# Board_C22.net
KiCad netlist of a schematic drawn in Altium Designer
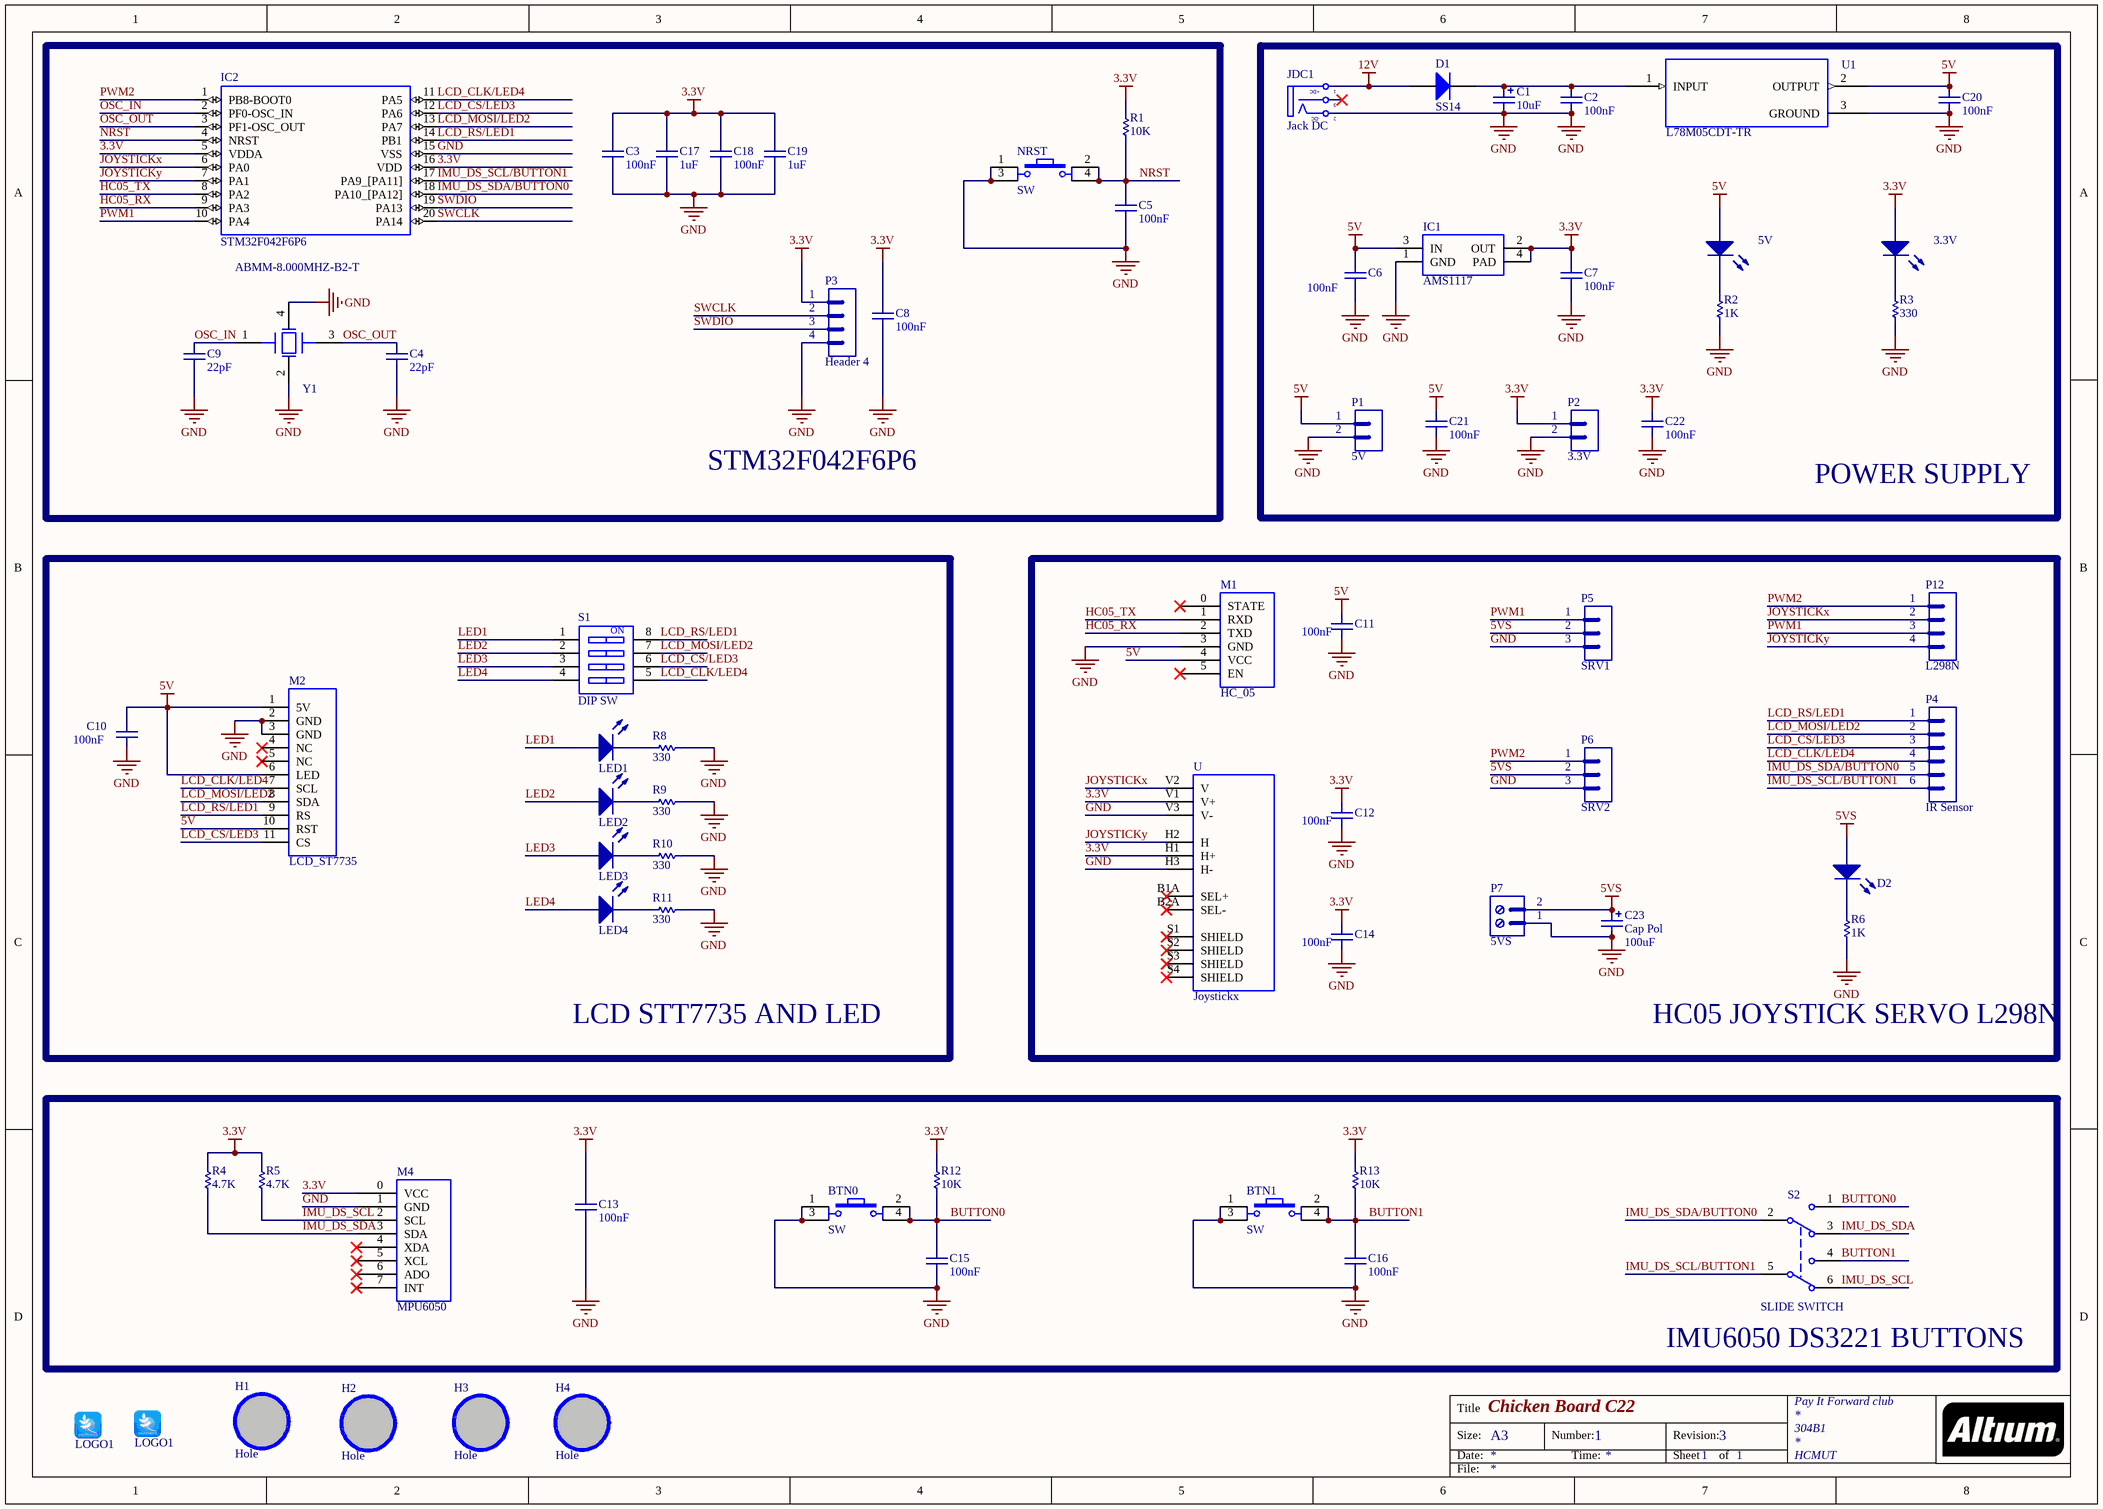
[diagram p0: Board_C22.SchDoc]

(export (version "E")
  (design (tool "Eeschema 10.0.6"))
  (components
    (comp (ref "3.3V") (value "LED") (footprint "LED_0805_Blue") (libsource (lib "Board_C22") (part "LED")))
    (comp (ref "5V") (value "LED") (footprint "LED_0805_Blue") (libsource (lib "Board_C22") (part "LED")))
    (comp (ref "BTN0")
      (value "SW")
      (footprint "4301x60437x6")
      (description "Switch button 4 pin")
      (libsource (lib "Board_C22") (part "SW4"))
    )
    (comp (ref "BTN1")
      (value "SW")
      (footprint "4301x60437x6")
      (description "Switch button 4 pin")
      (libsource (lib "Board_C22") (part "SW4"))
    )
    (comp (ref "C1")
      (value "Capacitors")
      (footprint "C_TANTALUM_3216_18")
      (description "Capacitors Tantalum")
      (fields
        (field (name "MANUFACTURER") "Kemet")
        (field (name "MANUFACTURER PART NUMBER") "T491A106K010AT")
        (field (name "CAPACITANCE") "10uF")
      )
      (libsource (lib "Board_C22") (part "Cap Pol Tantalum"))
    )
    (comp (ref "C2")
      (value "100nF")
      (footprint "CAP-SM-0805")
      (description "Capacitor")
      (fields (field (name "Comment") "Cap Non-Pol SMD"))
      (libsource (lib "Board_C22") (part "Cap Non-Pol SMD"))
    )
    (comp (ref "C3")
      (value "100nF")
      (footprint "CAP-SM-0805")
      (description "Capacitor")
      (fields (field (name "Comment") "Cap Non-Pol SMD"))
      (libsource (lib "Board_C22") (part "Cap Non-Pol SMD"))
    )
    (comp (ref "C4")
      (value "22pF")
      (footprint "CAP-SM-0805")
      (description "Capacitor")
      (fields (field (name "Comment") "Cap Non-Pol SMD"))
      (libsource (lib "Board_C22") (part "Cap Non-Pol SMD"))
    )
    (comp (ref "C5")
      (value "100nF")
      (footprint "CAP-SM-0805")
      (description "Capacitor")
      (fields (field (name "Comment") "Cap Non-Pol SMD"))
      (libsource (lib "Board_C22") (part "Cap Non-Pol SMD"))
    )
    (comp (ref "C6")
      (value "100nF")
      (footprint "CAP-SM-0805")
      (description "Capacitor")
      (fields (field (name "Comment") "Cap Non-Pol SMD"))
      (libsource (lib "Board_C22") (part "Cap Non-Pol SMD"))
    )
    (comp (ref "C7")
      (value "100nF")
      (footprint "CAP-SM-0805")
      (description "Capacitor")
      (fields (field (name "Comment") "Cap Non-Pol SMD"))
      (libsource (lib "Board_C22") (part "Cap Non-Pol SMD"))
    )
    (comp (ref "C8")
      (value "100nF")
      (footprint "CAP-SM-0805")
      (description "Capacitor")
      (fields (field (name "Comment") "Cap Non-Pol SMD"))
      (libsource (lib "Board_C22") (part "Cap Non-Pol SMD"))
    )
    (comp (ref "C9")
      (value "22pF")
      (footprint "CAP-SM-0805")
      (description "Capacitor")
      (fields (field (name "Comment") "Cap Non-Pol SMD"))
      (libsource (lib "Board_C22") (part "Cap Non-Pol SMD"))
    )
    (comp (ref "C10")
      (value "100nF")
      (footprint "CAP-SM-0805")
      (description "Capacitor")
      (fields (field (name "Comment") "Cap Non-Pol SMD"))
      (libsource (lib "Board_C22") (part "Cap Non-Pol SMD"))
    )
    (comp (ref "C11")
      (value "100nF")
      (footprint "CAP-SM-0805")
      (description "Capacitor")
      (fields (field (name "Comment") "Cap Non-Pol SMD"))
      (libsource (lib "Board_C22") (part "Cap Non-Pol SMD"))
    )
    (comp (ref "C12")
      (value "100nF")
      (footprint "CAP-SM-0805")
      (description "Capacitor")
      (fields (field (name "Comment") "Cap Non-Pol SMD"))
      (libsource (lib "Board_C22") (part "Cap Non-Pol SMD"))
    )
    (comp (ref "C13")
      (value "100nF")
      (footprint "CAP-SM-0805")
      (description "Capacitor")
      (fields (field (name "Comment") "Cap Non-Pol SMD"))
      (libsource (lib "Board_C22") (part "Cap Non-Pol SMD"))
    )
    (comp (ref "C14")
      (value "100nF")
      (footprint "CAP-SM-0805")
      (description "Capacitor")
      (fields (field (name "Comment") "Cap Non-Pol SMD"))
      (libsource (lib "Board_C22") (part "Cap Non-Pol SMD"))
    )
    (comp (ref "C15")
      (value "100nF")
      (footprint "CAP-SM-0805")
      (description "Capacitor")
      (fields (field (name "Comment") "Cap Non-Pol SMD"))
      (libsource (lib "Board_C22") (part "Cap Non-Pol SMD"))
    )
    (comp (ref "C16")
      (value "100nF")
      (footprint "CAP-SM-0805")
      (description "Capacitor")
      (fields (field (name "Comment") "Cap Non-Pol SMD"))
      (libsource (lib "Board_C22") (part "Cap Non-Pol SMD"))
    )
    (comp (ref "C17")
      (value "1uF")
      (footprint "CAP-SM-0805")
      (description "Capacitor")
      (fields (field (name "Comment") "Cap Non-Pol SMD"))
      (libsource (lib "Board_C22") (part "Cap Non-Pol SMD"))
    )
    (comp (ref "C18")
      (value "100nF")
      (footprint "CAP-SM-0805")
      (description "Capacitor")
      (fields (field (name "Comment") "Cap Non-Pol SMD"))
      (libsource (lib "Board_C22") (part "Cap Non-Pol SMD"))
    )
    (comp (ref "C19")
      (value "1uF")
      (footprint "CAP-SM-0805")
      (description "Capacitor")
      (fields (field (name "Comment") "Cap Non-Pol SMD"))
      (libsource (lib "Board_C22") (part "Cap Non-Pol SMD"))
    )
    (comp (ref "C20")
      (value "100nF")
      (footprint "CAP-SM-0805")
      (description "Capacitor")
      (fields (field (name "Comment") "Cap Non-Pol SMD"))
      (libsource (lib "Board_C22") (part "Cap Non-Pol SMD"))
    )
    (comp (ref "C21")
      (value "100nF")
      (footprint "CAP-SM-0805")
      (description "Capacitor")
      (fields (field (name "Comment") "Cap Non-Pol SMD"))
      (libsource (lib "Board_C22") (part "Cap Non-Pol SMD"))
    )
    (comp (ref "C22")
      (value "100nF")
      (footprint "CAP-SM-0805")
      (description "Capacitor")
      (fields (field (name "Comment") "Cap Non-Pol SMD"))
      (libsource (lib "Board_C22") (part "Cap Non-Pol SMD"))
    )
    (comp (ref "C23")
      (value "Cap Pol")
      (footprint "CP1/2.5")
      (description "Polarized Capacitor (Radial)")
      (fields (field (name "ALTIUM_VALUE") "100uF"))
      (libsource (lib "Board_C22") (part "Cap Pol"))
    )
    (comp (ref "D1")
      (value "SS14")
      (footprint "SS14")
      (description "DIODE SCHOTTKY 40V 1A SMA")
      (fields (field (name "MANUFACTURER") "ON Semiconductor"))
      (libsource (lib "Board_C22") (part "Diode-SS14"))
    )
    (comp (ref "D2") (value "LED") (footprint "LED_0805_Blue") (libsource (lib "Board_C22") (part "LED")))
    (comp (ref "H1")
      (value "Hole")
      (footprint "LO KHOAN 3MM")
      (description "Hole 3mm")
      (libsource (lib "Board_C22") (part "Hole"))
    )
    (comp (ref "H2")
      (value "Hole")
      (footprint "LO KHOAN 3MM")
      (description "Hole 3mm")
      (libsource (lib "Board_C22") (part "Hole"))
    )
    (comp (ref "H3")
      (value "Hole")
      (footprint "LO KHOAN 3MM")
      (description "Hole 3mm")
      (libsource (lib "Board_C22") (part "Hole"))
    )
    (comp (ref "H4")
      (value "Hole")
      (footprint "LO KHOAN 3MM")
      (description "Hole 3mm")
      (libsource (lib "Board_C22") (part "Hole"))
    )
    (comp (ref "IC1")
      (value "AMS1117")
      (footprint "SOT223")
      (description "Available in 1.8V, 2.5V, 2.85V, 3.3V, 5V, and  Adjustable Versions")
      (libsource (lib "Board_C22") (part "AMS1117"))
    )
    (comp (ref "IC2")
      (value "STM32F042F6P6")
      (footprint "TSSOP20")
      (description "ARMÂ® CortexÂ®-M0 STM32F0 Microcontroller IC 32-Bit 48MHz 32KB _32K x 8_ FLASH 20-TSSOP")
      (fields (field (name "MF") "STMicroelectronics"))
      (libsource (lib "Board_C22") (part "STM32F042F6P6"))
    )
    (comp (ref "JDC1")
      (value "Jack DC")
      (footprint "DC-IN")
      (description "Jack DC input")
      (libsource (lib "Board_C22") (part "Jack DC"))
    )
    (comp (ref "LED1") (value "LED") (footprint "LED_0805_Blue") (libsource (lib "Board_C22") (part "LED")))
    (comp (ref "LED2") (value "LED") (footprint "LED_0805_Blue") (libsource (lib "Board_C22") (part "LED")))
    (comp (ref "LED3") (value "LED") (footprint "LED_0805_Blue") (libsource (lib "Board_C22") (part "LED")))
    (comp (ref "LED4") (value "LED") (footprint "LED_0805_Blue") (libsource (lib "Board_C22") (part "LED")))
    (comp (ref "M1") (value "HC_05") (footprint "HC_05") (libsource (lib "Board_C22") (part "HC_05")))
    (comp (ref "M2")
      (value "LCD_ST7735")
      (footprint "LCD_ST7735")
      (libsource (lib "Board_C22") (part "LCD_ST7735"))
    )
    (comp (ref "M4")
      (value "MPU6050")
      (footprint "GY521_MPU6050")
      (libsource (lib "Board_C22") (part "GY521_MPU6050"))
    )
    (comp (ref "NRST")
      (value "SW")
      (footprint "4301x60437x6")
      (description "Switch button 4 pin")
      (libsource (lib "Board_C22") (part "SW4"))
    )
    (comp (ref "P1")
      (value "5V")
      (footprint "JP2")
      (description "Header, 2-Pin")
      (fields (field (name "PUBLISHER") "Altium Limited"))
      (libsource (lib "Board_C22") (part "Header 2"))
    )
    (comp (ref "P2")
      (value "3.3V")
      (footprint "JP2")
      (description "Header, 2-Pin")
      (fields (field (name "PUBLISHER") "Altium Limited"))
      (libsource (lib "Board_C22") (part "Header 2"))
    )
    (comp (ref "P3")
      (value "Header 4")
      (footprint "JP4")
      (description "Header, 4-Pin")
      (fields (field (name "PUBLISHER") "Altium Limited"))
      (libsource (lib "Board_C22") (part "Header 4"))
    )
    (comp (ref "P4")
      (value "IR Sensor")
      (footprint "JP6")
      (description "Header, 6-Pin")
      (fields (field (name "PUBLISHER") "Altium Limited"))
      (libsource (lib "Board_C22") (part "Header 6"))
    )
    (comp (ref "P5")
      (value "SRV1")
      (footprint "JP3")
      (description "Header, 3-Pin")
      (fields (field (name "PUBLISHER") "Altium Limited"))
      (libsource (lib "Board_C22") (part "Header 3"))
    )
    (comp (ref "P6")
      (value "SRV2")
      (footprint "JP3")
      (description "Header, 3-Pin")
      (fields (field (name "PUBLISHER") "Altium Limited"))
      (libsource (lib "Board_C22") (part "Header 3"))
    )
    (comp (ref "P7")
      (value "5VS")
      (footprint "DOMINO SMALL 2")
      (description "Domino, 2-Pin")
      (fields (field (name "PUBLISHER") "Altium Limited"))
      (libsource (lib "Board_C22") (part "Domino 2"))
    )
    (comp (ref "P12")
      (value "L298N")
      (footprint "JP4")
      (description "Header, 4-Pin")
      (fields (field (name "PUBLISHER") "Altium Limited"))
      (libsource (lib "Board_C22") (part "Header 4"))
    )
    (comp (ref "R1")
      (value "10K")
      (footprint "RES-SM-0805")
      (fields (field (name "Comment") "Resistor 1/4W"))
      (libsource (lib "Board_C22") (part "RES"))
    )
    (comp (ref "R2")
      (value "1K")
      (footprint "RES-SM-0805")
      (fields (field (name "Comment") "Resistor 1/4W"))
      (libsource (lib "Board_C22") (part "RES"))
    )
    (comp (ref "R3")
      (value "330")
      (footprint "RES-SM-0805")
      (fields (field (name "Comment") "Resistor 1/4W"))
      (libsource (lib "Board_C22") (part "RES"))
    )
    (comp (ref "R4")
      (value "4.7K")
      (footprint "RES-SM-0805")
      (fields (field (name "Comment") "Resistor 1/4W"))
      (libsource (lib "Board_C22") (part "RES"))
    )
    (comp (ref "R5")
      (value "4.7K")
      (footprint "RES-SM-0805")
      (fields (field (name "Comment") "Resistor 1/4W"))
      (libsource (lib "Board_C22") (part "RES"))
    )
    (comp (ref "R6")
      (value "1K")
      (footprint "RES-SM-0805")
      (fields (field (name "Comment") "Resistor 1/4W"))
      (libsource (lib "Board_C22") (part "RES"))
    )
    (comp (ref "R8")
      (value "330")
      (footprint "RES-SM-0805")
      (fields (field (name "Comment") "Resistor 1/4W"))
      (libsource (lib "Board_C22") (part "RES"))
    )
    (comp (ref "R9")
      (value "330")
      (footprint "RES-SM-0805")
      (fields (field (name "Comment") "Resistor 1/4W"))
      (libsource (lib "Board_C22") (part "RES"))
    )
    (comp (ref "R10")
      (value "330")
      (footprint "RES-SM-0805")
      (fields (field (name "Comment") "Resistor 1/4W"))
      (libsource (lib "Board_C22") (part "RES"))
    )
    (comp (ref "R11")
      (value "330")
      (footprint "RES-SM-0805")
      (fields (field (name "Comment") "Resistor 1/4W"))
      (libsource (lib "Board_C22") (part "RES"))
    )
    (comp (ref "R12")
      (value "10K")
      (footprint "RES-SM-0805")
      (fields (field (name "Comment") "Resistor 1/4W"))
      (libsource (lib "Board_C22") (part "RES"))
    )
    (comp (ref "R13")
      (value "10K")
      (footprint "RES-SM-0805")
      (fields (field (name "Comment") "Resistor 1/4W"))
      (libsource (lib "Board_C22") (part "RES"))
    )
    (comp (ref "S1")
      (value "DIP SW")
      (footprint "418117270904")
      (description "WS-DITV Compact THT Dip Switch, Raised Actuator, pitch 2.54mm, 4p")
      (fields (field (name "PART NUMBER") "418117270904") (field (name "PUBLISHER") "Wurth Elektronik"))
      (libsource (lib "Board_C22") (part "DIP SW"))
    )
    (comp (ref "S2")
      (value "SLIDE SWITCH")
      (footprint "452404020202")
      (description "WS-SLTV THT Mini Slide Switch, Same Side Connection, DPDT")
      (fields (field (name "PART NUMBER") "452404020202") (field (name "PUBLISHER") "Wurth Elektronik"))
      (libsource (lib "Board_C22") (part "SW"))
    )
    (comp (ref "U")
      (value "Joystickx")
      (footprint "XDCR_COM-09032")
      (description "Joystick, 2 - Axis Analog _Resistive_ Output")
      (fields (field (name "MF") "SparkFun Electronics") (field (name "MP") "COM-09032"))
      (libsource (lib "Board_C22") (part "Joystickx"))
    )
    (comp (ref "U1")
      (value "L78M05CDT-TR")
      (footprint "DPAK_STM")
      (description "No Description Available")
      (fields (field (name "COPYRIGHT") "Copyright (C) 2018 Accelerated Designs. All rights reserved"))
      (libsource (lib "Board_C22") (part "L78M05CDT-TR"))
    )
    (comp (ref "Y1")
      (value "ABMM-8.000MHZ-B2-T")
      (footprint "XTAL_TSX-3225_16.0000MF18X-AC3")
      (description "8MHz Â±20ppm Crystal 18pF 70 Ohms 4-SMD, No Lead")
      (fields (field (name "MF") "Abracon") (field (name "DIGI-KEY_PART_NUMBER") "535-9164-1-ND"))
      (libsource (lib "Board_C22") (part "ABMM-8.000MHZ-B2-T"))
    )
  )
  (nets
    (net (code "1") (name "/BUTTON0") (class "Default")
      (node (ref "BTN0") (pin "2") (pintype "passive"))
      (node (ref "BTN0") (pin "4") (pintype "passive"))
      (node (ref "C15") (pin "2") (pinfunction "2_2") (pintype "passive"))
      (node (ref "R12") (pin "1") (pintype "passive"))
      (node (ref "S2") (pin "1") (pinfunction "1_1") (pintype "passive"))
    )
    (net (code "2") (name "/BUTTON1") (class "Default")
      (node (ref "BTN1") (pin "2") (pintype "passive"))
      (node (ref "BTN1") (pin "4") (pintype "passive"))
      (node (ref "C16") (pin "2") (pinfunction "2_2") (pintype "passive"))
      (node (ref "R13") (pin "1") (pintype "passive"))
      (node (ref "S2") (pin "4") (pinfunction "4_4") (pintype "passive"))
    )
    (net (code "3") (name "/HC05_RX") (class "Default")
      (node (ref "IC2") (pin "9") (pinfunction "PA3_9") (pintype "bidirectional"))
      (node (ref "M1") (pin "2") (pinfunction "TXD_2") (pintype "passive"))
    )
    (net (code "4") (name "/HC05_TX") (class "Default")
      (node (ref "IC2") (pin "8") (pinfunction "PA2_8") (pintype "bidirectional"))
      (node (ref "M1") (pin "1") (pinfunction "RXD_1") (pintype "passive"))
    )
    (net (code "5") (name "/IMU_DS_SCL") (class "Default")
      (node (ref "M4") (pin "2") (pinfunction "SCL_2") (pintype "passive"))
      (node (ref "R5") (pin "1") (pintype "passive"))
      (node (ref "S2") (pin "6") (pinfunction "6_6") (pintype "passive"))
    )
    (net (code "6") (name "/IMU_DS_SCL{slash}BUTTON1") (class "Default")
      (node (ref "IC2") (pin "17") (pinfunction "PA9_[PA11]_17") (pintype "bidirectional"))
      (node (ref "P4") (pin "6") (pinfunction "6_6") (pintype "passive"))
      (node (ref "S2") (pin "5") (pinfunction "COM_5") (pintype "passive"))
    )
    (net (code "7") (name "/IMU_DS_SDA") (class "Default")
      (node (ref "M4") (pin "3") (pinfunction "SDA_3") (pintype "passive"))
      (node (ref "R4") (pin "1") (pintype "passive"))
      (node (ref "S2") (pin "3") (pinfunction "3_3") (pintype "passive"))
    )
    (net (code "8") (name "/IMU_DS_SDA{slash}BUTTON0") (class "Default")
      (node (ref "IC2") (pin "18") (pinfunction "PA10_[PA12]_18") (pintype "bidirectional"))
      (node (ref "P4") (pin "5") (pinfunction "5_5") (pintype "passive"))
      (node (ref "S2") (pin "2") (pinfunction "COM_2") (pintype "passive"))
    )
    (net (code "9") (name "/JOYSTICKx") (class "Default")
      (node (ref "IC2") (pin "6") (pinfunction "PA0_6") (pintype "bidirectional"))
      (node (ref "P12") (pin "2") (pinfunction "2_2") (pintype "passive"))
      (node (ref "U") (pin "V2") (pinfunction "V_V2") (pintype "passive"))
    )
    (net (code "10") (name "/JOYSTICKy") (class "Default")
      (node (ref "IC2") (pin "7") (pinfunction "PA1_7") (pintype "bidirectional"))
      (node (ref "P12") (pin "4") (pinfunction "4_4") (pintype "passive"))
      (node (ref "U") (pin "H2") (pinfunction "H_H2") (pintype "passive"))
    )
    (net (code "11") (name "/LCD_CLK{slash}LED4") (class "Default")
      (node (ref "IC2") (pin "11") (pinfunction "PA5_11") (pintype "bidirectional"))
      (node (ref "M2") (pin "7") (pinfunction "SCL_7") (pintype "passive"))
      (node (ref "P4") (pin "4") (pinfunction "4_4") (pintype "passive"))
      (node (ref "S1") (pin "5") (pinfunction "5_5") (pintype "passive"))
    )
    (net (code "12") (name "/LCD_CS{slash}LED3") (class "Default")
      (node (ref "IC2") (pin "12") (pinfunction "PA6_12") (pintype "bidirectional"))
      (node (ref "M2") (pin "11") (pinfunction "CS_11") (pintype "passive"))
      (node (ref "P4") (pin "3") (pinfunction "3_3") (pintype "passive"))
      (node (ref "S1") (pin "6") (pinfunction "6_6") (pintype "passive"))
    )
    (net (code "13") (name "/LCD_MOSI{slash}LED2") (class "Default")
      (node (ref "IC2") (pin "13") (pinfunction "PA7_13") (pintype "bidirectional"))
      (node (ref "M2") (pin "8") (pinfunction "SDA_8") (pintype "passive"))
      (node (ref "P4") (pin "2") (pinfunction "2_2") (pintype "passive"))
      (node (ref "S1") (pin "7") (pinfunction "7_7") (pintype "passive"))
    )
    (net (code "14") (name "/LCD_RS{slash}LED1") (class "Default")
      (node (ref "IC2") (pin "14") (pinfunction "PB1_14") (pintype "bidirectional"))
      (node (ref "M2") (pin "9") (pinfunction "RS_9") (pintype "passive"))
      (node (ref "P4") (pin "1") (pinfunction "1_1") (pintype "passive"))
      (node (ref "S1") (pin "8") (pinfunction "8_8") (pintype "passive"))
    )
    (net (code "15") (name "/LED1") (class "Default")
      (node (ref "LED1") (pin "1") (pinfunction "A_1") (pintype "passive"))
      (node (ref "S1") (pin "1") (pinfunction "1_1") (pintype "passive"))
    )
    (net (code "16") (name "/LED2") (class "Default")
      (node (ref "LED2") (pin "1") (pinfunction "A_1") (pintype "passive"))
      (node (ref "S1") (pin "2") (pinfunction "2_2") (pintype "passive"))
    )
    (net (code "17") (name "/LED3") (class "Default")
      (node (ref "LED3") (pin "1") (pinfunction "A_1") (pintype "passive"))
      (node (ref "S1") (pin "3") (pinfunction "3_3") (pintype "passive"))
    )
    (net (code "18") (name "/LED4") (class "Default")
      (node (ref "LED4") (pin "1") (pinfunction "A_1") (pintype "passive"))
      (node (ref "S1") (pin "4") (pinfunction "4_4") (pintype "passive"))
    )
    (net (code "19") (name "/NRST") (class "Default")
      (node (ref "C5") (pin "2") (pinfunction "2_2") (pintype "passive"))
      (node (ref "IC2") (pin "4") (pinfunction "NRST_4") (pintype "bidirectional"))
      (node (ref "NRST") (pin "2") (pintype "passive"))
      (node (ref "NRST") (pin "4") (pintype "passive"))
      (node (ref "R1") (pin "1") (pintype "passive"))
    )
    (net (code "20") (name "/OSC_IN") (class "Default")
      (node (ref "C9") (pin "1") (pinfunction "1_1") (pintype "passive"))
      (node (ref "IC2") (pin "2") (pinfunction "PF0-OSC_IN_2") (pintype "bidirectional"))
      (node (ref "Y1") (pin "1") (pintype "passive"))
    )
    (net (code "21") (name "/OSC_OUT") (class "Default")
      (node (ref "C4") (pin "2") (pinfunction "2_2") (pintype "passive"))
      (node (ref "IC2") (pin "3") (pinfunction "PF1-OSC_OUT_3") (pintype "bidirectional"))
      (node (ref "Y1") (pin "3") (pintype "passive"))
    )
    (net (code "22") (name "/PWM1") (class "Default")
      (node (ref "IC2") (pin "10") (pinfunction "PA4_10") (pintype "bidirectional"))
      (node (ref "P12") (pin "3") (pinfunction "3_3") (pintype "passive"))
      (node (ref "P5") (pin "1") (pinfunction "1_1") (pintype "passive"))
    )
    (net (code "23") (name "/PWM2") (class "Default")
      (node (ref "IC2") (pin "1") (pinfunction "PB8-BOOT0_1") (pintype "bidirectional"))
      (node (ref "P12") (pin "1") (pinfunction "1_1") (pintype "passive"))
      (node (ref "P6") (pin "1") (pinfunction "1_1") (pintype "passive"))
    )
    (net (code "24") (name "/SWCLK") (class "Default")
      (node (ref "IC2") (pin "20") (pinfunction "PA14_20") (pintype "bidirectional"))
      (node (ref "P3") (pin "2") (pinfunction "2_2") (pintype "passive"))
    )
    (net (code "25") (name "/SWDIO") (class "Default")
      (node (ref "IC2") (pin "19") (pinfunction "PA13_19") (pintype "bidirectional"))
      (node (ref "P3") (pin "3") (pinfunction "3_3") (pintype "passive"))
    )
    (net (code "26") (name "3.3V") (class "Default")
      (node (ref "3.3V") (pin "1") (pinfunction "A_1") (pintype "passive"))
      (node (ref "C12") (pin "2") (pinfunction "2_2") (pintype "passive"))
      (node (ref "C13") (pin "2") (pinfunction "2_2") (pintype "passive"))
      (node (ref "C14") (pin "2") (pinfunction "2_2") (pintype "passive"))
      (node (ref "C17") (pin "2") (pinfunction "2_2") (pintype "passive"))
      (node (ref "C18") (pin "2") (pinfunction "2_2") (pintype "passive"))
      (node (ref "C19") (pin "2") (pinfunction "2_2") (pintype "passive"))
      (node (ref "C22") (pin "2") (pinfunction "2_2") (pintype "passive"))
      (node (ref "C3") (pin "2") (pinfunction "2_2") (pintype "passive"))
      (node (ref "C7") (pin "2") (pinfunction "2_2") (pintype "passive"))
      (node (ref "C8") (pin "2") (pinfunction "2_2") (pintype "passive"))
      (node (ref "IC1") (pin "2") (pinfunction "OUT_2") (pintype "passive"))
      (node (ref "IC1") (pin "4") (pinfunction "PAD_4") (pintype "passive"))
      (node (ref "IC2") (pin "16") (pinfunction "VDD_16") (pintype "bidirectional"))
      (node (ref "IC2") (pin "5") (pinfunction "VDDA_5") (pintype "bidirectional"))
      (node (ref "M4") (pin "0") (pinfunction "VCC_0") (pintype "passive"))
      (node (ref "P2") (pin "1") (pinfunction "1_1") (pintype "passive"))
      (node (ref "P3") (pin "1") (pinfunction "1_1") (pintype "passive"))
      (node (ref "R1") (pin "2") (pintype "passive"))
      (node (ref "R12") (pin "2") (pintype "passive"))
      (node (ref "R13") (pin "2") (pintype "passive"))
      (node (ref "R4") (pin "2") (pintype "passive"))
      (node (ref "R5") (pin "2") (pintype "passive"))
      (node (ref "U") (pin "H1") (pinfunction "H+_H1") (pintype "passive"))
      (node (ref "U") (pin "V1") (pinfunction "V+_V1") (pintype "passive"))
    )
    (net (code "27") (name "5V") (class "Default")
      (node (ref "5V") (pin "1") (pinfunction "A_1") (pintype "passive"))
      (node (ref "C10") (pin "2") (pinfunction "2_2") (pintype "passive"))
      (node (ref "C11") (pin "2") (pinfunction "2_2") (pintype "passive"))
      (node (ref "C20") (pin "1") (pinfunction "1_1") (pintype "passive"))
      (node (ref "C21") (pin "2") (pinfunction "2_2") (pintype "passive"))
      (node (ref "C6") (pin "2") (pinfunction "2_2") (pintype "passive"))
      (node (ref "IC1") (pin "3") (pinfunction "IN_3") (pintype "passive"))
      (node (ref "M1") (pin "4") (pinfunction "VCC_4") (pintype "passive"))
      (node (ref "M2") (pin "1") (pinfunction "5V_1") (pintype "passive"))
      (node (ref "M2") (pin "10") (pinfunction "RST_10") (pintype "passive"))
      (node (ref "M2") (pin "6") (pinfunction "LED_6") (pintype "passive"))
      (node (ref "P1") (pin "1") (pinfunction "1_1") (pintype "passive"))
      (node (ref "U1") (pin "2") (pinfunction "OUTPUT_2") (pintype "output"))
    )
    (net (code "28") (name "5VS") (class "Default")
      (node (ref "C23") (pin "1") (pinfunction "1_1") (pintype "passive"))
      (node (ref "D2") (pin "1") (pinfunction "A_1") (pintype "passive"))
      (node (ref "P5") (pin "2") (pinfunction "2_2") (pintype "passive"))
      (node (ref "P6") (pin "2") (pinfunction "2_2") (pintype "passive"))
      (node (ref "P7") (pin "2") (pinfunction "2_2") (pintype "passive"))
    )
    (net (code "29") (name "12V") (class "Default")
      (node (ref "D1") (pin "1") (pinfunction "A_1") (pintype "passive"))
      (node (ref "JDC1") (pin "1") (pinfunction "T_1") (pintype "passive"))
    )
    (net (code "30") (name "GND") (class "Default")
      (node (ref "BTN0") (pin "1") (pintype "passive"))
      (node (ref "BTN0") (pin "3") (pintype "passive"))
      (node (ref "BTN1") (pin "1") (pintype "passive"))
      (node (ref "BTN1") (pin "3") (pintype "passive"))
      (node (ref "C1") (pin "2") (pinfunction "2_2") (pintype "passive"))
      (node (ref "C10") (pin "1") (pinfunction "1_1") (pintype "passive"))
      (node (ref "C11") (pin "1") (pinfunction "1_1") (pintype "passive"))
      (node (ref "C12") (pin "1") (pinfunction "1_1") (pintype "passive"))
      (node (ref "C13") (pin "1") (pinfunction "1_1") (pintype "passive"))
      (node (ref "C14") (pin "1") (pinfunction "1_1") (pintype "passive"))
      (node (ref "C15") (pin "1") (pinfunction "1_1") (pintype "passive"))
      (node (ref "C16") (pin "1") (pinfunction "1_1") (pintype "passive"))
      (node (ref "C17") (pin "1") (pinfunction "1_1") (pintype "passive"))
      (node (ref "C18") (pin "1") (pinfunction "1_1") (pintype "passive"))
      (node (ref "C19") (pin "1") (pinfunction "1_1") (pintype "passive"))
      (node (ref "C2") (pin "1") (pinfunction "1_1") (pintype "passive"))
      (node (ref "C20") (pin "2") (pinfunction "2_2") (pintype "passive"))
      (node (ref "C21") (pin "1") (pinfunction "1_1") (pintype "passive"))
      (node (ref "C22") (pin "1") (pinfunction "1_1") (pintype "passive"))
      (node (ref "C23") (pin "2") (pinfunction "2_2") (pintype "passive"))
      (node (ref "C3") (pin "1") (pinfunction "1_1") (pintype "passive"))
      (node (ref "C4") (pin "1") (pinfunction "1_1") (pintype "passive"))
      (node (ref "C5") (pin "1") (pinfunction "1_1") (pintype "passive"))
      (node (ref "C6") (pin "1") (pinfunction "1_1") (pintype "passive"))
      (node (ref "C7") (pin "1") (pinfunction "1_1") (pintype "passive"))
      (node (ref "C8") (pin "1") (pinfunction "1_1") (pintype "passive"))
      (node (ref "C9") (pin "2") (pinfunction "2_2") (pintype "passive"))
      (node (ref "IC1") (pin "1") (pinfunction "GND_1") (pintype "passive"))
      (node (ref "IC2") (pin "15") (pinfunction "VSS_15") (pintype "bidirectional"))
      (node (ref "JDC1") (pin "2") (pinfunction "TN_2") (pintype "passive"))
      (node (ref "M1") (pin "3") (pinfunction "GND_3") (pintype "passive"))
      (node (ref "M2") (pin "2") (pinfunction "GND_2") (pintype "passive"))
      (node (ref "M2") (pin "3") (pinfunction "GND_3") (pintype "passive"))
      (node (ref "M4") (pin "1") (pinfunction "GND_1") (pintype "passive"))
      (node (ref "NRST") (pin "1") (pintype "passive"))
      (node (ref "NRST") (pin "3") (pintype "passive"))
      (node (ref "P1") (pin "2") (pinfunction "2_2") (pintype "passive"))
      (node (ref "P2") (pin "2") (pinfunction "2_2") (pintype "passive"))
      (node (ref "P3") (pin "4") (pinfunction "4_4") (pintype "passive"))
      (node (ref "P5") (pin "3") (pinfunction "3_3") (pintype "passive"))
      (node (ref "P6") (pin "3") (pinfunction "3_3") (pintype "passive"))
      (node (ref "P7") (pin "1") (pinfunction "1_1") (pintype "passive"))
      (node (ref "R10") (pin "1") (pintype "passive"))
      (node (ref "R11") (pin "1") (pintype "passive"))
      (node (ref "R2") (pin "1") (pintype "passive"))
      (node (ref "R3") (pin "1") (pintype "passive"))
      (node (ref "R6") (pin "1") (pintype "passive"))
      (node (ref "R8") (pin "1") (pintype "passive"))
      (node (ref "R9") (pin "1") (pintype "passive"))
      (node (ref "U") (pin "H3") (pinfunction "H-_H3") (pintype "passive"))
      (node (ref "U") (pin "V3") (pinfunction "V-_V3") (pintype "passive"))
      (node (ref "U1") (pin "3") (pinfunction "GROUND_3") (pintype "passive"))
      (node (ref "Y1") (pin "2") (pintype "passive"))
      (node (ref "Y1") (pin "4") (pintype "passive"))
    )
    (net (code "31") (name "Net-(3.3V-K)") (class "Default")
      (node (ref "3.3V") (pin "2") (pinfunction "K_2") (pintype "passive"))
      (node (ref "R3") (pin "2") (pintype "passive"))
    )
    (net (code "32") (name "Net-(5V-K)") (class "Default")
      (node (ref "5V") (pin "2") (pinfunction "K_2") (pintype "passive"))
      (node (ref "R2") (pin "2") (pintype "passive"))
    )
    (net (code "33") (name "Net-(D1-K)") (class "Default")
      (node (ref "C1") (pin "1") (pinfunction "1_1") (pintype "passive"))
      (node (ref "C2") (pin "2") (pinfunction "2_2") (pintype "passive"))
      (node (ref "D1") (pin "2") (pinfunction "K_2") (pintype "passive"))
      (node (ref "U1") (pin "1") (pinfunction "INPUT_1") (pintype "input"))
    )
    (net (code "34") (name "Net-(D2-K)") (class "Default")
      (node (ref "D2") (pin "2") (pinfunction "K_2") (pintype "passive"))
      (node (ref "R6") (pin "2") (pintype "passive"))
    )
    (net (code "35") (name "Net-(LED1-K)") (class "Default")
      (node (ref "LED1") (pin "2") (pinfunction "K_2") (pintype "passive"))
      (node (ref "R8") (pin "2") (pintype "passive"))
    )
    (net (code "36") (name "Net-(LED2-K)") (class "Default")
      (node (ref "LED2") (pin "2") (pinfunction "K_2") (pintype "passive"))
      (node (ref "R9") (pin "2") (pintype "passive"))
    )
    (net (code "37") (name "Net-(LED3-K)") (class "Default")
      (node (ref "LED3") (pin "2") (pinfunction "K_2") (pintype "passive"))
      (node (ref "R10") (pin "2") (pintype "passive"))
    )
    (net (code "38") (name "Net-(LED4-K)") (class "Default")
      (node (ref "LED4") (pin "2") (pinfunction "K_2") (pintype "passive"))
      (node (ref "R11") (pin "2") (pintype "passive"))
    )
    (net (code "39") (name "unconnected-(H1-Pad1)") (class "Default")
      (node (ref "H1") (pin "1") (pinfunction "1_1") (pintype "passive"))
    )
    (net (code "40") (name "unconnected-(H2-Pad1)") (class "Default")
      (node (ref "H2") (pin "1") (pinfunction "1_1") (pintype "passive"))
    )
    (net (code "41") (name "unconnected-(H3-Pad1)") (class "Default")
      (node (ref "H3") (pin "1") (pinfunction "1_1") (pintype "passive"))
    )
    (net (code "42") (name "unconnected-(H4-Pad1)") (class "Default")
      (node (ref "H4") (pin "1") (pinfunction "1_1") (pintype "passive"))
    )
    (net (code "43") (name "unconnected-(JDC1-S-Pad3)") (class "Default")
      (node (ref "JDC1") (pin "3") (pinfunction "S_3") (pintype "power_in+no_connect"))
    )
    (net (code "44") (name "unconnected-(M1-EN-Pad5)") (class "Default")
      (node (ref "M1") (pin "5") (pinfunction "EN_5") (pintype "passive+no_connect"))
    )
    (net (code "45") (name "unconnected-(M1-STATE-Pad0)") (class "Default")
      (node (ref "M1") (pin "0") (pinfunction "STATE_0") (pintype "passive+no_connect"))
    )
    (net (code "46") (name "unconnected-(M2-NC-Pad4)") (class "Default")
      (node (ref "M2") (pin "4") (pinfunction "NC_4") (pintype "passive+no_connect"))
    )
    (net (code "47") (name "unconnected-(M2-NC-Pad5)") (class "Default")
      (node (ref "M2") (pin "5") (pinfunction "NC_5") (pintype "passive+no_connect"))
    )
    (net (code "48") (name "unconnected-(M4-ADO-Pad6)") (class "Default")
      (node (ref "M4") (pin "6") (pinfunction "ADO_6") (pintype "passive+no_connect"))
    )
    (net (code "49") (name "unconnected-(M4-INT-Pad7)") (class "Default")
      (node (ref "M4") (pin "7") (pinfunction "INT_7") (pintype "passive+no_connect"))
    )
    (net (code "50") (name "unconnected-(M4-XCL-Pad5)") (class "Default")
      (node (ref "M4") (pin "5") (pinfunction "XCL_5") (pintype "passive+no_connect"))
    )
    (net (code "51") (name "unconnected-(M4-XDA-Pad4)") (class "Default")
      (node (ref "M4") (pin "4") (pinfunction "XDA_4") (pintype "passive+no_connect"))
    )
    (net (code "52") (name "unconnected-(U-SEL+-PadB1A)") (class "Default")
      (node (ref "U") (pin "B1A") (pinfunction "SEL+_B1A") (pintype "passive+no_connect"))
    )
    (net (code "53") (name "unconnected-(U-SEL--PadB2A)") (class "Default")
      (node (ref "U") (pin "B2A") (pinfunction "SEL-_B2A") (pintype "passive+no_connect"))
    )
    (net (code "54") (name "unconnected-(U-SHIELD-PadS1)") (class "Default")
      (node (ref "U") (pin "S1") (pinfunction "SHIELD_S1") (pintype "passive+no_connect"))
    )
    (net (code "55") (name "unconnected-(U-SHIELD-PadS2)") (class "Default")
      (node (ref "U") (pin "S2") (pinfunction "SHIELD_S2") (pintype "passive+no_connect"))
    )
    (net (code "56") (name "unconnected-(U-SHIELD-PadS3)") (class "Default")
      (node (ref "U") (pin "S3") (pinfunction "SHIELD_S3") (pintype "passive+no_connect"))
    )
    (net (code "57") (name "unconnected-(U-SHIELD-PadS4)") (class "Default")
      (node (ref "U") (pin "S4") (pinfunction "SHIELD_S4") (pintype "passive+no_connect"))
    )
  )
)
